# Adapter.net
KiCad netlist of a schematic drawn in Altium Designer
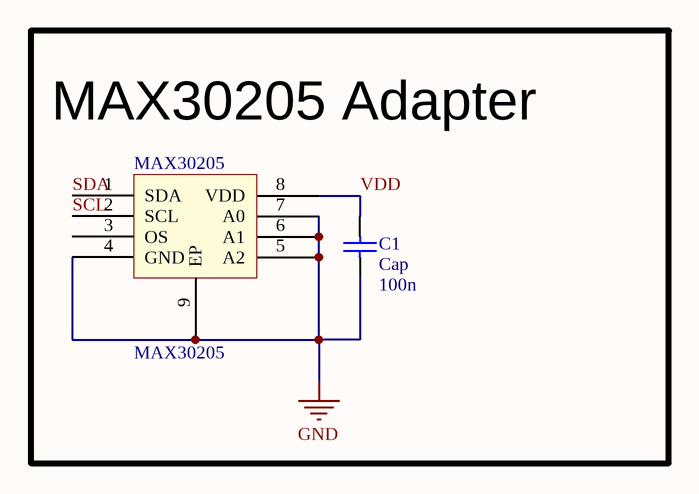
[diagram p0: Adapter.SchDoc]

(export (version "E")
  (design (tool "Eeschema 10.0.6"))
  (components
    (comp (ref "C1")
      (value "Cap")
      (footprint "0603 Cap")
      (fields (field (name "ALTIUM_VALUE") "100n"))
      (libsource (lib "B105rlc") (part "Cap"))
    )
    (comp (ref "MAX30206")
      (value "MAX30205")
      (footprint "Smartstrap_with_MAX30205:MAX30205")
      (fields (field (name "SUPPLIER PART NUMBER 1") "MAX30205"))
      (libsource (lib "Smartstrap_with_MAX30205") (part "MAX30205"))
    )
  )
  (nets
    (net (code "1") (name "/SCL") (class "Default")
      (node (ref "MAX30206") (pin "2") (pinfunction "SCL_2") (pintype "passive"))
    )
    (net (code "2") (name "/SDA") (class "Default")
      (node (ref "MAX30206") (pin "1") (pinfunction "SDA_1") (pintype "passive"))
    )
    (net (code "3") (name "/VDD") (class "Default")
      (node (ref "C1") (pin "2") (pinfunction "2_2") (pintype "passive"))
      (node (ref "MAX30206") (pin "8") (pinfunction "VDD_8") (pintype "passive"))
    )
    (net (code "4") (name "GND") (class "Default")
      (node (ref "C1") (pin "1") (pinfunction "1_1") (pintype "passive"))
      (node (ref "MAX30206") (pin "4") (pinfunction "GND_4") (pintype "passive"))
      (node (ref "MAX30206") (pin "5") (pinfunction "A2_5") (pintype "passive"))
      (node (ref "MAX30206") (pin "6") (pinfunction "A1_6") (pintype "passive"))
      (node (ref "MAX30206") (pin "7") (pinfunction "A0_7") (pintype "passive"))
      (node (ref "MAX30206") (pin "9") (pinfunction "EP_9") (pintype "passive"))
    )
    (net (code "5") (name "unconnected-(MAX30206-OS-Pad3)") (class "Default")
      (node (ref "MAX30206") (pin "3") (pinfunction "OS_3") (pintype "passive"))
    )
  )
)
